# ChameleonMini-RevG.net
KiCad netlist of a schematic drawn in EAGLE
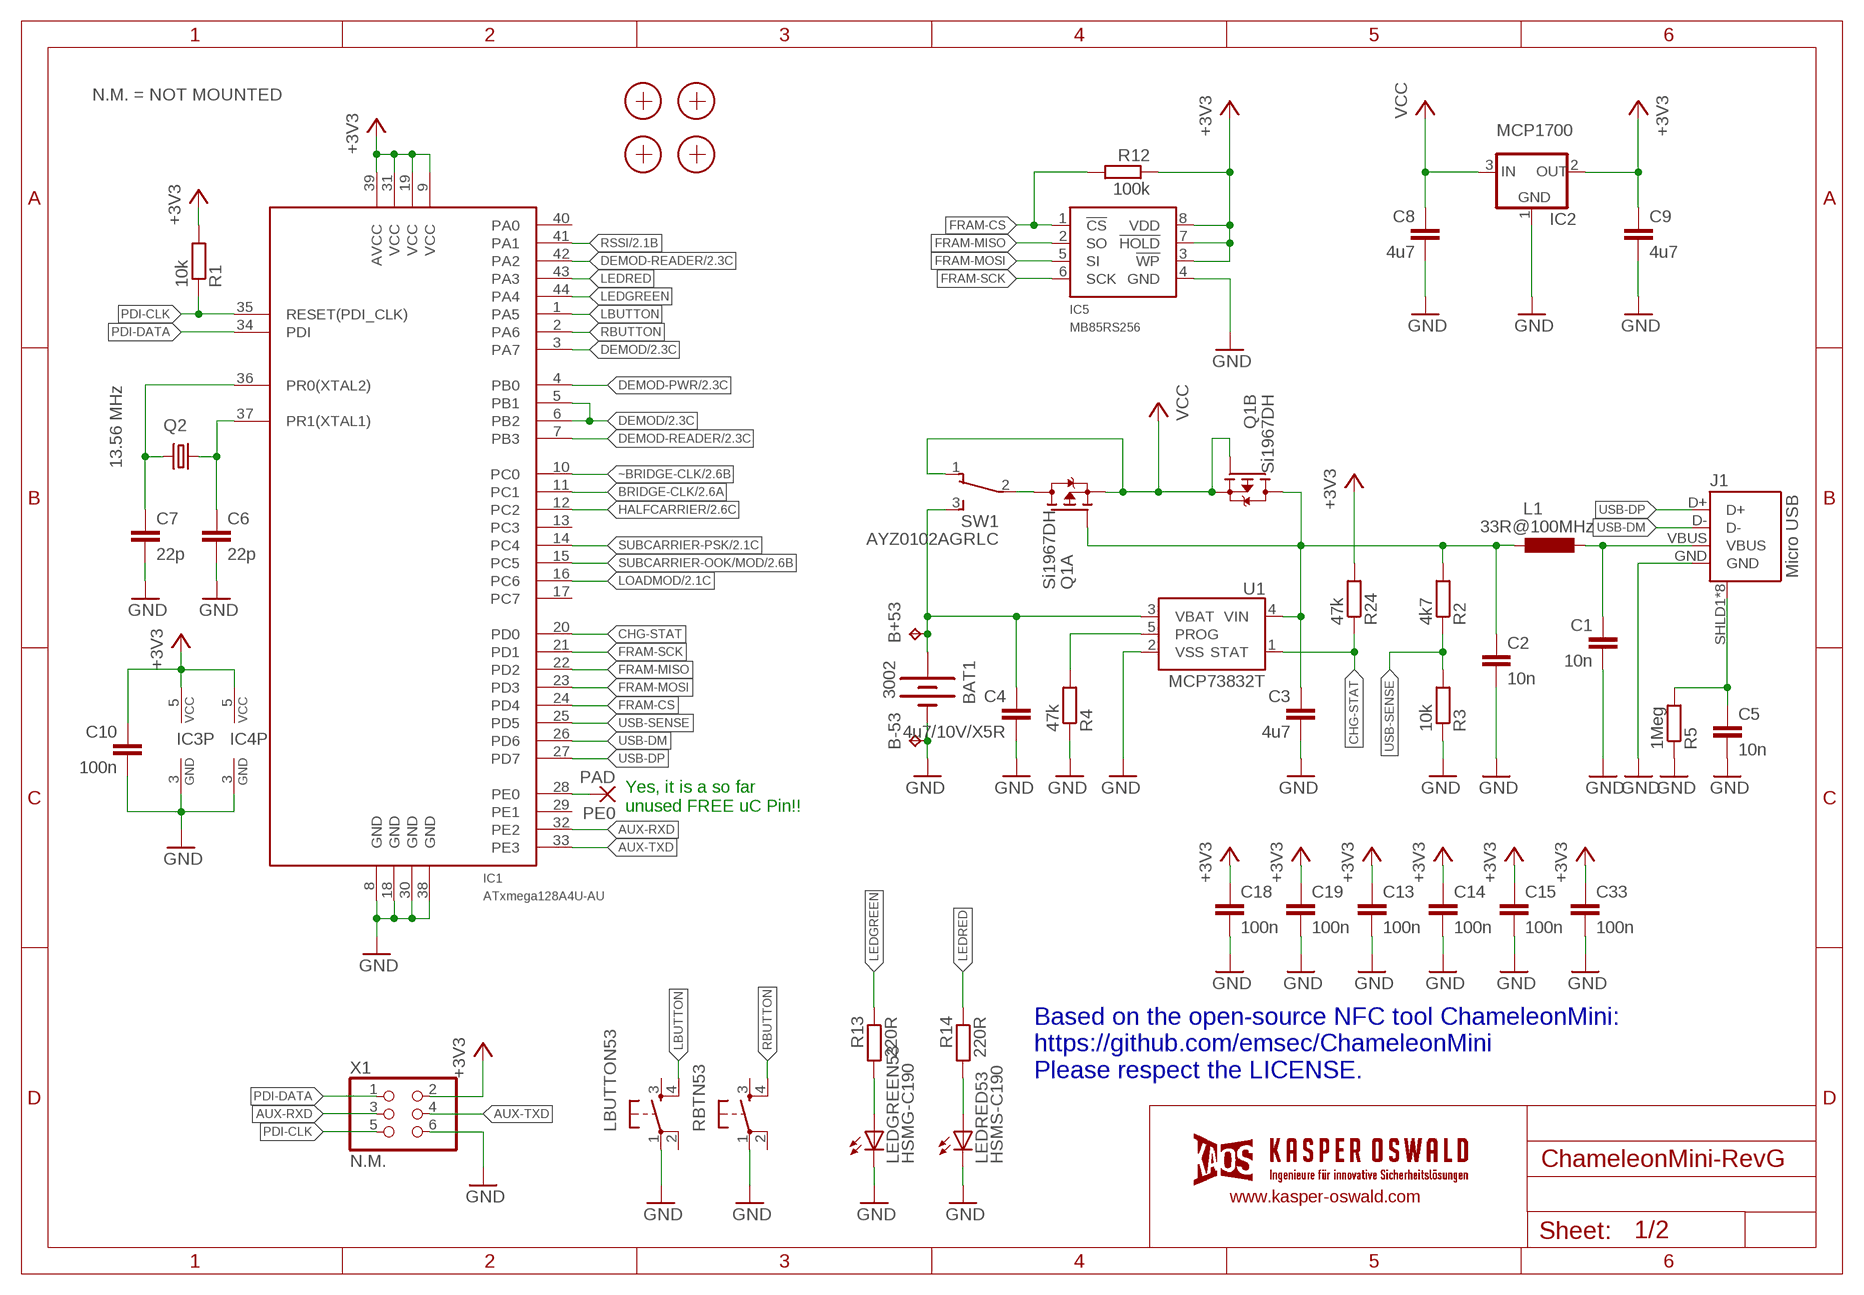
[diagram p0: schematic, sheet 1]
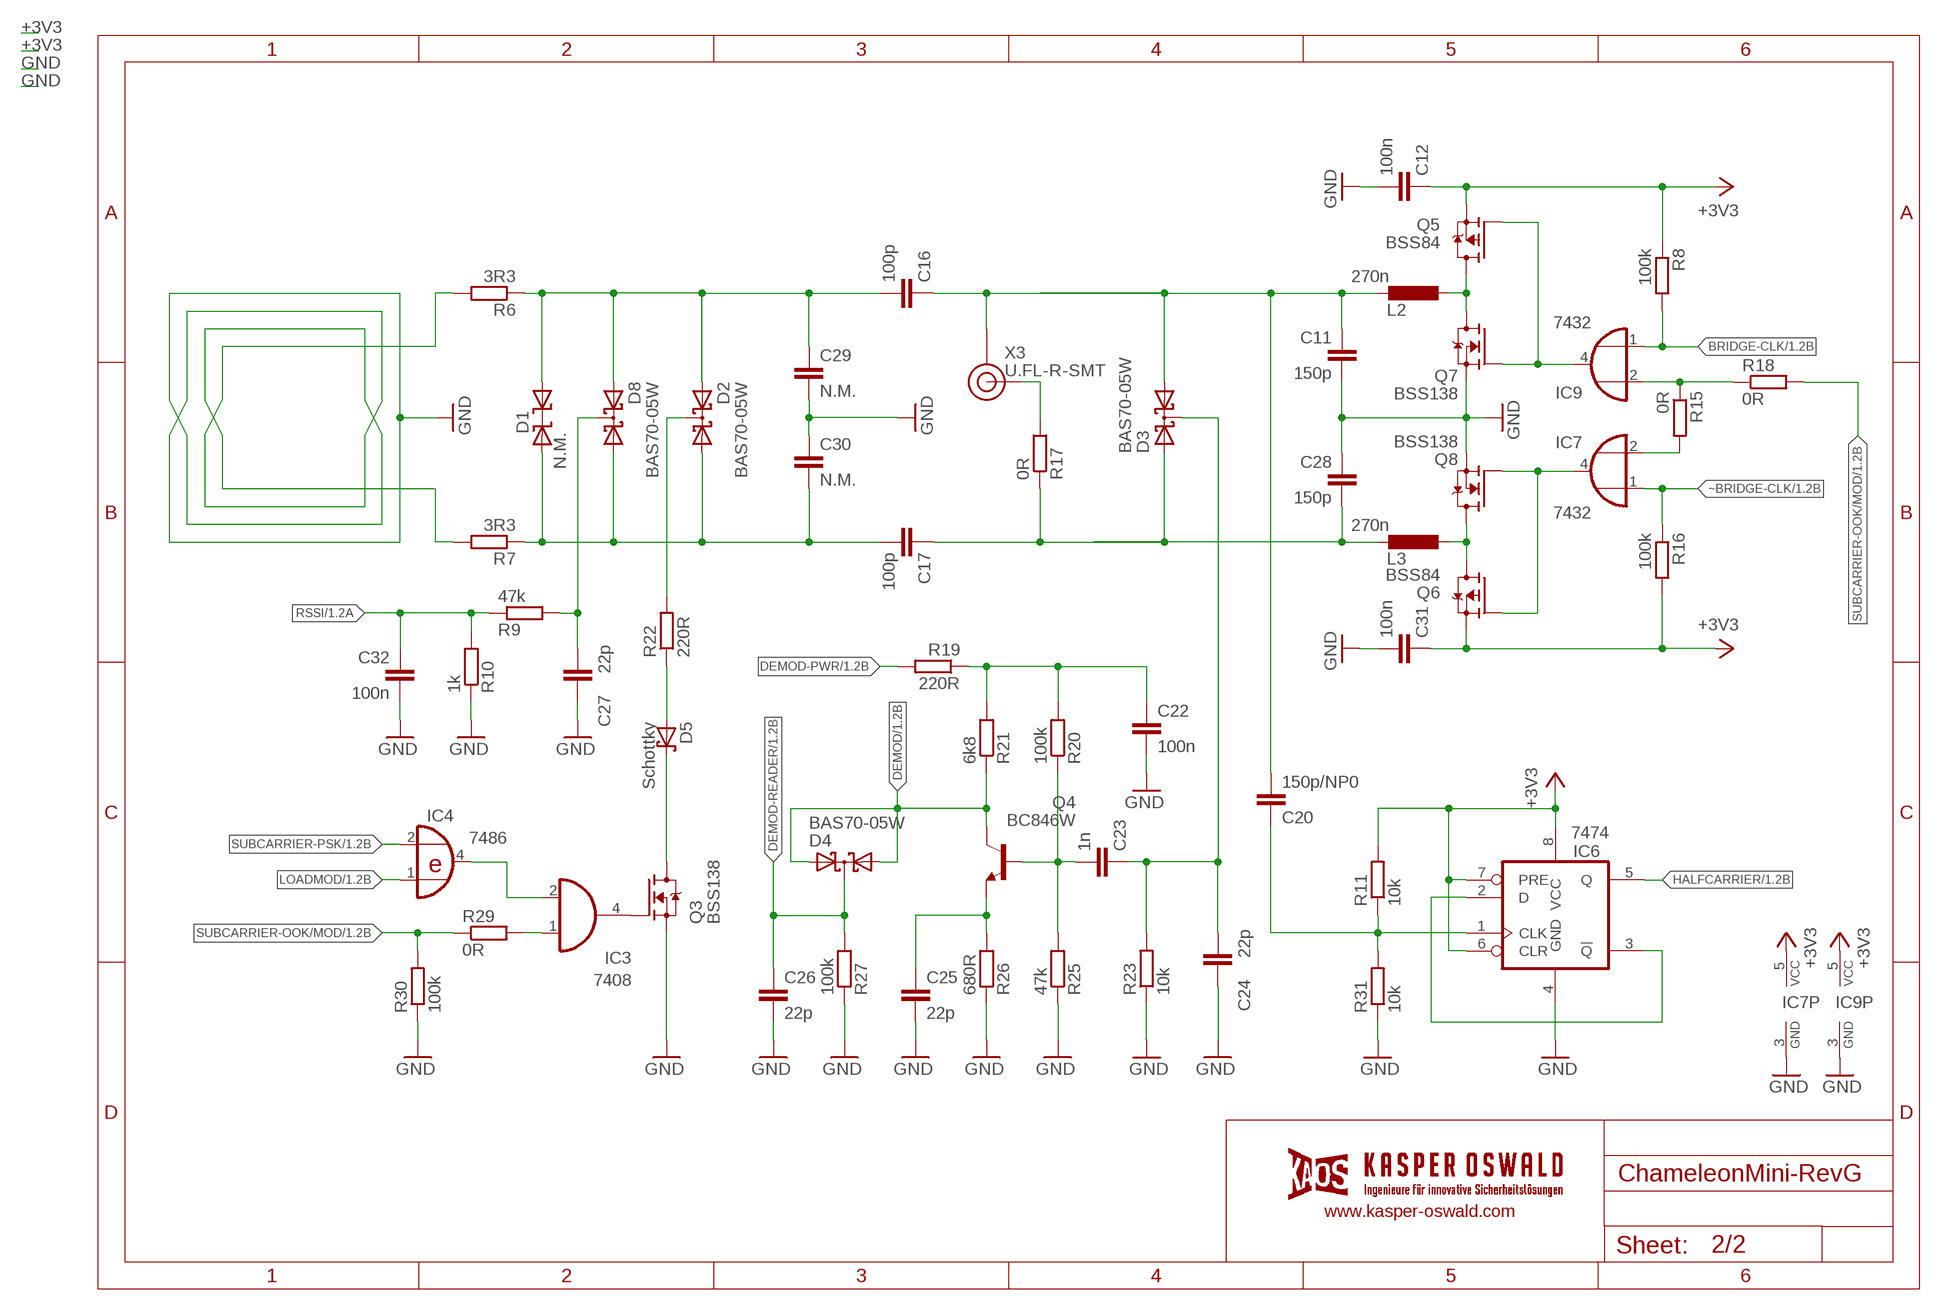
[diagram p1: schematic, sheet 2]

(export (version "E")
  (design (tool "Eeschema 10.0.6"))
  (components
    (comp (ref "C11")
      (value "150p")
      (footprint "eagle-import:C0603K")
      (libsource (lib "eagle-import") (part "C-EUC0603K"))
    )
    (comp (ref "C12")
      (value "100n")
      (footprint "eagle-import:C0603K")
      (libsource (lib "eagle-import") (part "C-EUC0603K"))
    )
    (comp (ref "C16")
      (value "100p")
      (footprint "eagle-import:C0603K")
      (libsource (lib "eagle-import") (part "C-EUC0603K"))
    )
    (comp (ref "C17")
      (value "100p")
      (footprint "eagle-import:C0603K")
      (libsource (lib "eagle-import") (part "C-EUC0603K"))
    )
    (comp (ref "C20")
      (value "150p/NP0")
      (footprint "eagle-import:C0603K")
      (libsource (lib "eagle-import") (part "C-EUC0603K"))
    )
    (comp (ref "C22")
      (value "100n")
      (footprint "eagle-import:C0603K")
      (libsource (lib "eagle-import") (part "C-EUC0603K"))
    )
    (comp (ref "C23")
      (value "1n")
      (footprint "eagle-import:C0603K")
      (libsource (lib "eagle-import") (part "C-EUC0603K"))
    )
    (comp (ref "C24")
      (value "22p")
      (footprint "eagle-import:C0603K")
      (libsource (lib "eagle-import") (part "C-EUC0603K"))
    )
    (comp (ref "C25")
      (value "22p")
      (footprint "eagle-import:C0603K")
      (libsource (lib "eagle-import") (part "C-EUC0603K"))
    )
    (comp (ref "C26")
      (value "22p")
      (footprint "eagle-import:C0603K")
      (libsource (lib "eagle-import") (part "C-EUC0603K"))
    )
    (comp (ref "C27")
      (value "22p")
      (footprint "eagle-import:C0603K")
      (libsource (lib "eagle-import") (part "C-EUC0603K"))
    )
    (comp (ref "C28")
      (value "150p")
      (footprint "eagle-import:C0603K")
      (libsource (lib "eagle-import") (part "C-EUC0603K"))
    )
    (comp (ref "C29")
      (value "N.M.")
      (footprint "eagle-import:C0603K")
      (libsource (lib "eagle-import") (part "C-EUC0603K"))
    )
    (comp (ref "C30")
      (value "N.M.")
      (footprint "eagle-import:C0603K")
      (libsource (lib "eagle-import") (part "C-EUC0603K"))
    )
    (comp (ref "C31")
      (value "100n")
      (footprint "eagle-import:C0603K")
      (libsource (lib "eagle-import") (part "C-EUC0603K"))
    )
    (comp (ref "C32")
      (value "100n")
      (footprint "eagle-import:C0603K")
      (libsource (lib "eagle-import") (part "C-EUC0603K"))
    )
    (comp (ref "D1")
      (value "N.M.")
      (footprint "eagle-import:DO214AC")
      (libsource (lib "eagle-import") (part "SMAJ"))
    )
    (comp (ref "D2")
      (value "BAS70-05W")
      (footprint "eagle-import:SOT323")
      (libsource (lib "eagle-import") (part "BAS70-05W"))
    )
    (comp (ref "D3")
      (value "BAS70-05W")
      (footprint "eagle-import:SOT323")
      (libsource (lib "eagle-import") (part "BAS70-05W"))
    )
    (comp (ref "D4")
      (value "BAS70-05W")
      (footprint "eagle-import:SOT323")
      (libsource (lib "eagle-import") (part "BAS70-05W"))
    )
    (comp (ref "D5")
      (value "Schottky")
      (footprint "eagle-import:SOD323(F)")
      (libsource (lib "eagle-import") (part "1PS76SB70"))
    )
    (comp (ref "D8")
      (value "BAS70-05W")
      (footprint "eagle-import:SOT323")
      (libsource (lib "eagle-import") (part "BAS70-05W"))
    )
    (comp (ref "IC3")
      (value "7408")
      (footprint "eagle-import:SC70-5")
      (libsource (lib "eagle-import") (part "741G08DCKLVC"))
    )
    (comp (ref "IC4")
      (value "7486")
      (footprint "eagle-import:SC70-5")
      (libsource (lib "eagle-import") (part "741G86DCKAHC"))
    )
    (comp (ref "IC6")
      (value "7474")
      (footprint "eagle-import:VSSOP8")
      (libsource (lib "eagle-import") (part "74LVC1G74DC"))
    )
    (comp (ref "IC7")
      (value "7432")
      (footprint "eagle-import:SC70-5")
      (libsource (lib "eagle-import") (part "741G32DCKAHC"))
    )
    (comp (ref "IC9")
      (value "7432")
      (footprint "eagle-import:SC70-5")
      (libsource (lib "eagle-import") (part "741G32DCKAHC"))
    )
    (comp (ref "L2")
      (value "270n")
      (footprint "eagle-import:L2012C")
      (libsource (lib "eagle-import") (part "L-EUL2012C"))
    )
    (comp (ref "L3")
      (value "270n")
      (footprint "eagle-import:L2012C")
      (libsource (lib "eagle-import") (part "L-EUL2012C"))
    )
    (comp (ref "Q3")
      (value "BSS138")
      (footprint "eagle-import:SOT323")
      (libsource (lib "eagle-import") (part "BSS138BKW"))
    )
    (comp (ref "Q4")
      (value "BC846W")
      (footprint "eagle-import:SOT323")
      (libsource (lib "eagle-import") (part "BC84XW"))
    )
    (comp (ref "Q5")
      (value "BSS84")
      (footprint "eagle-import:SOT323")
      (libsource (lib "eagle-import") (part "BSS84AKW"))
    )
    (comp (ref "Q6")
      (value "BSS84")
      (footprint "eagle-import:SOT323")
      (libsource (lib "eagle-import") (part "BSS84AKW"))
    )
    (comp (ref "Q7")
      (value "BSS138")
      (footprint "eagle-import:SOT323")
      (libsource (lib "eagle-import") (part "BSS138BKW"))
    )
    (comp (ref "Q8")
      (value "BSS138")
      (footprint "eagle-import:SOT323")
      (libsource (lib "eagle-import") (part "BSS138BKW"))
    )
    (comp (ref "R6")
      (value "3R3")
      (footprint "eagle-import:R0603")
      (libsource (lib "eagle-import") (part "R-EU_R0603"))
    )
    (comp (ref "R7")
      (value "3R3")
      (footprint "eagle-import:R0603")
      (libsource (lib "eagle-import") (part "R-EU_R0603"))
    )
    (comp (ref "R8")
      (value "100k")
      (footprint "eagle-import:R0603")
      (libsource (lib "eagle-import") (part "R-EU_R0603"))
    )
    (comp (ref "R9")
      (value "47k")
      (footprint "eagle-import:R0603")
      (libsource (lib "eagle-import") (part "R-EU_R0603"))
    )
    (comp (ref "R10")
      (value "1k")
      (footprint "eagle-import:R0603")
      (libsource (lib "eagle-import") (part "R-EU_R0603"))
    )
    (comp (ref "R11")
      (value "10k")
      (footprint "eagle-import:R0603")
      (libsource (lib "eagle-import") (part "R-EU_R0603"))
    )
    (comp (ref "R15")
      (value "0R")
      (footprint "eagle-import:R0603")
      (libsource (lib "eagle-import") (part "R-EU_R0603"))
    )
    (comp (ref "R16")
      (value "100k")
      (footprint "eagle-import:R0603")
      (libsource (lib "eagle-import") (part "R-EU_R0603"))
    )
    (comp (ref "R17")
      (value "0R")
      (footprint "eagle-import:R0603")
      (libsource (lib "eagle-import") (part "R-EU_R0603"))
    )
    (comp (ref "R18")
      (value "0R")
      (footprint "eagle-import:R0603")
      (libsource (lib "eagle-import") (part "R-EU_R0603"))
    )
    (comp (ref "R19")
      (value "220R")
      (footprint "eagle-import:R0603")
      (libsource (lib "eagle-import") (part "R-EU_R0603"))
    )
    (comp (ref "R20")
      (value "100k")
      (footprint "eagle-import:R0603")
      (libsource (lib "eagle-import") (part "R-EU_R0603"))
    )
    (comp (ref "R21")
      (value "6k8")
      (footprint "eagle-import:R0603")
      (libsource (lib "eagle-import") (part "R-EU_R0603"))
    )
    (comp (ref "R22")
      (value "220R")
      (footprint "eagle-import:R0603")
      (libsource (lib "eagle-import") (part "R-EU_R0603"))
    )
    (comp (ref "R23")
      (value "10k")
      (footprint "eagle-import:R0603")
      (libsource (lib "eagle-import") (part "R-EU_R0603"))
    )
    (comp (ref "R25")
      (value "47k")
      (footprint "eagle-import:R0603")
      (libsource (lib "eagle-import") (part "R-EU_R0603"))
    )
    (comp (ref "R26")
      (value "680R")
      (footprint "eagle-import:R0603")
      (libsource (lib "eagle-import") (part "R-EU_R0603"))
    )
    (comp (ref "R27")
      (value "100k")
      (footprint "eagle-import:R0603")
      (libsource (lib "eagle-import") (part "R-EU_R0603"))
    )
    (comp (ref "R29")
      (value "0R")
      (footprint "eagle-import:R0603")
      (libsource (lib "eagle-import") (part "R-EU_R0603"))
    )
    (comp (ref "R30")
      (value "100k")
      (footprint "eagle-import:R0603")
      (libsource (lib "eagle-import") (part "R-EU_R0603"))
    )
    (comp (ref "R31")
      (value "10k")
      (footprint "eagle-import:R0603")
      (libsource (lib "eagle-import") (part "R-EU_R0603"))
    )
    (comp (ref "X3")
      (value "U.FL-R-SMT")
      (footprint "eagle-import:U.FL-R-SMT")
      (libsource (lib "eagle-import") (part "U.FL-R-SMT"))
    )
    (comp (ref "B+53")
      (value "TPTP18SQ")
      (footprint "eagle-import:TP18SQ")
      (libsource (lib "eagle-import") (part "TPTP18SQ"))
    )
    (comp (ref "B-53")
      (value "TPTP18SQ")
      (footprint "eagle-import:TP18SQ")
      (libsource (lib "eagle-import") (part "TPTP18SQ"))
    )
    (comp (ref "BAT1")
      (value "3002")
      (footprint "eagle-import:BATTCON_20MM")
      (libsource (lib "eagle-import") (part "3002"))
    )
    (comp (ref "C1")
      (value "10n")
      (footprint "eagle-import:C1206K")
      (libsource (lib "eagle-import") (part "C-EUC1206K"))
    )
    (comp (ref "C2")
      (value "10n")
      (footprint "eagle-import:C1206K")
      (libsource (lib "eagle-import") (part "C-EUC1206K"))
    )
    (comp (ref "C3")
      (value "4u7")
      (footprint "eagle-import:C0603K")
      (libsource (lib "eagle-import") (part "C-EUC0603K"))
    )
    (comp (ref "C4")
      (value "4u7/10V/X5R")
      (footprint "eagle-import:C0603K")
      (libsource (lib "eagle-import") (part "C-EUC0603K"))
    )
    (comp (ref "C5")
      (value "10n")
      (footprint "eagle-import:C0603K")
      (libsource (lib "eagle-import") (part "C-EUC0603K"))
    )
    (comp (ref "C6")
      (value "22p")
      (footprint "eagle-import:C0603K")
      (libsource (lib "eagle-import") (part "C-EUC0603K"))
    )
    (comp (ref "C7")
      (value "22p")
      (footprint "eagle-import:C0603K")
      (libsource (lib "eagle-import") (part "C-EUC0603K"))
    )
    (comp (ref "C8")
      (value "4u7")
      (footprint "eagle-import:C0603K")
      (libsource (lib "eagle-import") (part "C-EUC0603K"))
    )
    (comp (ref "C9")
      (value "4u7")
      (footprint "eagle-import:C0603K")
      (libsource (lib "eagle-import") (part "C-EUC0603K"))
    )
    (comp (ref "C10")
      (value "100n")
      (footprint "eagle-import:C0603K")
      (libsource (lib "eagle-import") (part "C-EUC0603K"))
    )
    (comp (ref "C13")
      (value "100n")
      (footprint "eagle-import:C0603K")
      (libsource (lib "eagle-import") (part "C-EUC0603K"))
    )
    (comp (ref "C14")
      (value "100n")
      (footprint "eagle-import:C0603K")
      (libsource (lib "eagle-import") (part "C-EUC0603K"))
    )
    (comp (ref "C15")
      (value "100n")
      (footprint "eagle-import:C0603K")
      (libsource (lib "eagle-import") (part "C-EUC0603K"))
    )
    (comp (ref "C18")
      (value "100n")
      (footprint "eagle-import:C0603K")
      (libsource (lib "eagle-import") (part "C-EUC0603K"))
    )
    (comp (ref "C19")
      (value "100n")
      (footprint "eagle-import:C0603K")
      (libsource (lib "eagle-import") (part "C-EUC0603K"))
    )
    (comp (ref "C33")
      (value "100n")
      (footprint "eagle-import:C0603K")
      (libsource (lib "eagle-import") (part "C-EUC0603K"))
    )
    (comp (ref "IC1")
      (value "ATxmega128A4U-AU")
      (footprint "eagle-import:TQFP44")
      (libsource (lib "eagle-import") (part "ATXMEGA_A4-A"))
    )
    (comp (ref "IC2")
      (value "MCP1700")
      (footprint "eagle-import:SOT23")
      (libsource (lib "eagle-import") (part "MCP1702"))
    )
    (comp (ref "IC5")
      (value "MB85RS256")
      (footprint "eagle-import:SO-08")
      (libsource (lib "eagle-import") (part "MB85RS"))
    )
    (comp (ref "J1")
      (value "Micro USB")
      (footprint "eagle-import:USB-MICROB-10118194")
      (libsource (lib "eagle-import") (part "USB-MICROB-2"))
    )
    (comp (ref "L1")
      (value "33R@100MHz")
      (footprint "eagle-import:L2012C")
      (libsource (lib "eagle-import") (part "L-EUL2012C"))
    )
    (comp (ref "LBUTTON53")
      (value "SWITCH_SPST_4_PINSQUARE")
      (footprint "eagle-import:TACTILE-SWITCH-SMD")
      (libsource (lib "eagle-import") (part "SWITCH_SPST_4_PINSQUARE"))
    )
    (comp (ref "LEDGREEN53")
      (value "HSMG-C190")
      (footprint "eagle-import:CHIPLED-0603")
      (libsource (lib "eagle-import") (part "LED-0603"))
    )
    (comp (ref "LEDRED53")
      (value "HSMS-C190")
      (footprint "eagle-import:CHIPLED-0603")
      (libsource (lib "eagle-import") (part "LED-0603"))
    )
    (comp (ref "PE0")
      (value "PAD")
      (footprint "eagle-import:SMD1,27-2,54")
      (libsource (lib "eagle-import") (part "WIREPADSMD1,27-254"))
    )
    (comp (ref "Q1")
      (value "Si1967DH")
      (footprint "eagle-import:SOT363")
      (libsource (lib "eagle-import") (part "BSS84AKS"))
    )
    (comp (ref "Q2")
      (value "13.56 MHz")
      (footprint "eagle-import:5MMX3.2MM")
      (libsource (lib "eagle-import") (part "TXC7B"))
    )
    (comp (ref "R1")
      (value "10k")
      (footprint "eagle-import:R0603")
      (libsource (lib "eagle-import") (part "R-EU_R0603"))
    )
    (comp (ref "R2")
      (value "4k7")
      (footprint "eagle-import:R0603")
      (libsource (lib "eagle-import") (part "R-EU_R0603"))
    )
    (comp (ref "R3")
      (value "10k")
      (footprint "eagle-import:R0603")
      (libsource (lib "eagle-import") (part "R-EU_R0603"))
    )
    (comp (ref "R4")
      (value "47k")
      (footprint "eagle-import:R0603")
      (libsource (lib "eagle-import") (part "R-EU_R0603"))
    )
    (comp (ref "R5")
      (value "1Meg")
      (footprint "eagle-import:R0603")
      (libsource (lib "eagle-import") (part "R-EU_R0603"))
    )
    (comp (ref "R12")
      (value "100k")
      (footprint "eagle-import:R0603")
      (libsource (lib "eagle-import") (part "R-EU_R0603"))
    )
    (comp (ref "R13")
      (value "220R")
      (footprint "eagle-import:R0603")
      (libsource (lib "eagle-import") (part "R-EU_R0603"))
    )
    (comp (ref "R14")
      (value "220R")
      (footprint "eagle-import:R0603")
      (libsource (lib "eagle-import") (part "R-EU_R0603"))
    )
    (comp (ref "R24")
      (value "47k")
      (footprint "eagle-import:R0603")
      (libsource (lib "eagle-import") (part "R-EU_R0603"))
    )
    (comp (ref "RBTN53")
      (value "SWITCH_SPST_4_PINSQUARE")
      (footprint "eagle-import:TACTILE-SWITCH-SMD")
      (libsource (lib "eagle-import") (part "SWITCH_SPST_4_PINSQUARE"))
    )
    (comp (ref "SW1")
      (value "AYZ0102AGRLC")
      (footprint "eagle-import:AYZ0102AGRLC")
      (libsource (lib "eagle-import") (part "AYZ0102AGRLC"))
    )
    (comp (ref "U1")
      (value "MCP73832T")
      (footprint "eagle-import:SOT23-5")
      (libsource (lib "eagle-import") (part "MCP73831"))
    )
    (comp (ref "X1")
      (value "N.M.")
      (footprint "eagle-import:PINHD-2X3-2.54-EDGE")
      (libsource (lib "eagle-import") (part "PINHD-2X3-2.54-EDGE"))
    )
    (comp (ref "X2")
      (value "PASSER-07")
      (footprint "eagle-import:PASSER_07MM")
      (libsource (lib "eagle-import") (part "PASSER-07"))
    )
    (comp (ref "X4")
      (value "PASSER-07")
      (footprint "eagle-import:PASSER_07MM")
      (libsource (lib "eagle-import") (part "PASSER-07"))
    )
    (comp (ref "X5")
      (value "PASSER-07")
      (footprint "eagle-import:PASSER_07MM")
      (libsource (lib "eagle-import") (part "PASSER-07"))
    )
    (comp (ref "X6")
      (value "PASSER-07")
      (footprint "eagle-import:PASSER_07MM")
      (libsource (lib "eagle-import") (part "PASSER-07"))
    )
  )
  (nets
    (net (code "1") (name "+3V3") (class "Default")
      (node (ref "C10") (pin "1") (pinfunction "1_1") (pintype "passive"))
      (node (ref "C12") (pin "1") (pinfunction "1_1") (pintype "passive"))
      (node (ref "C13") (pin "1") (pinfunction "1_1") (pintype "passive"))
      (node (ref "C14") (pin "1") (pinfunction "1_1") (pintype "passive"))
      (node (ref "C15") (pin "1") (pinfunction "1_1") (pintype "passive"))
      (node (ref "C18") (pin "1") (pinfunction "1_1") (pintype "passive"))
      (node (ref "C19") (pin "1") (pinfunction "1_1") (pintype "passive"))
      (node (ref "C31") (pin "1") (pinfunction "1_1") (pintype "passive"))
      (node (ref "C33") (pin "1") (pinfunction "1_1") (pintype "passive"))
      (node (ref "C9") (pin "1") (pinfunction "1_1") (pintype "passive"))
      (node (ref "IC1") (pin "19") (pinfunction "VCC_19") (pintype "bidirectional"))
      (node (ref "IC1") (pin "31") (pinfunction "VCC_31") (pintype "bidirectional"))
      (node (ref "IC1") (pin "39") (pinfunction "AVCC_39") (pintype "bidirectional"))
      (node (ref "IC1") (pin "9") (pinfunction "VCC_9") (pintype "bidirectional"))
      (node (ref "IC2") (pin "2") (pinfunction "OUT_2") (pintype "passive"))
      (node (ref "IC3") (pin "5") (pinfunction "VCC_5") (pintype "power_in"))
      (node (ref "IC4") (pin "5") (pinfunction "VCC_5") (pintype "power_in"))
      (node (ref "IC5") (pin "3") (pinfunction "~{WP}_3") (pintype "bidirectional"))
      (node (ref "IC5") (pin "7") (pinfunction "~{HOLD}_7") (pintype "bidirectional"))
      (node (ref "IC5") (pin "8") (pinfunction "VDD_8") (pintype "bidirectional"))
      (node (ref "IC6") (pin "6") (pinfunction "CLR_6") (pintype "input"))
      (node (ref "IC6") (pin "7") (pinfunction "PRE_7") (pintype "input"))
      (node (ref "IC6") (pin "8") (pinfunction "VCC_8") (pintype "bidirectional"))
      (node (ref "IC7") (pin "5") (pinfunction "VCC_5") (pintype "power_in"))
      (node (ref "IC9") (pin "5") (pinfunction "VCC_5") (pintype "power_in"))
      (node (ref "Q5") (pin "2") (pinfunction "S_2") (pintype "passive"))
      (node (ref "Q6") (pin "2") (pinfunction "S_2") (pintype "passive"))
      (node (ref "R1") (pin "2") (pinfunction "2_2") (pintype "passive"))
      (node (ref "R11") (pin "2") (pinfunction "2_2") (pintype "passive"))
      (node (ref "R12") (pin "1") (pinfunction "1_1") (pintype "passive"))
      (node (ref "R16") (pin "2") (pinfunction "2_2") (pintype "passive"))
      (node (ref "R24") (pin "2") (pinfunction "2_2") (pintype "passive"))
      (node (ref "R8") (pin "1") (pinfunction "1_1") (pintype "passive"))
      (node (ref "X1") (pin "2") (pinfunction "2_2") (pintype "passive"))
    )
    (net (code "2") (name "AUX-RXD") (class "Default")
      (node (ref "IC1") (pin "32") (pinfunction "PE2_32") (pintype "bidirectional"))
      (node (ref "X1") (pin "3") (pinfunction "3_3") (pintype "passive"))
    )
    (net (code "3") (name "AUX-TXD") (class "Default")
      (node (ref "IC1") (pin "33") (pinfunction "PE3_33") (pintype "bidirectional"))
      (node (ref "X1") (pin "4") (pinfunction "4_4") (pintype "passive"))
    )
    (net (code "4") (name "BRIDGE-CLK") (class "Default")
      (node (ref "IC1") (pin "11") (pinfunction "PC1_11") (pintype "bidirectional"))
      (node (ref "IC9") (pin "1") (pinfunction "I0_1") (pintype "input"))
      (node (ref "R8") (pin "2") (pinfunction "2_2") (pintype "passive"))
    )
    (net (code "5") (name "CHG-STAT") (class "Default")
      (node (ref "IC1") (pin "20") (pinfunction "PD0_20") (pintype "bidirectional"))
      (node (ref "R24") (pin "1") (pinfunction "1_1") (pintype "passive"))
      (node (ref "U1") (pin "1") (pinfunction "STAT_1") (pintype "output"))
    )
    (net (code "6") (name "DEMOD") (class "Default")
      (node (ref "D4") (pin "1") (pinfunction "A1_1") (pintype "passive"))
      (node (ref "D4") (pin "2") (pinfunction "A2_2") (pintype "passive"))
      (node (ref "IC1") (pin "3") (pinfunction "PA7_3") (pintype "bidirectional"))
      (node (ref "IC1") (pin "5") (pinfunction "PB1_5") (pintype "bidirectional"))
      (node (ref "IC1") (pin "6") (pinfunction "PB2_6") (pintype "bidirectional"))
      (node (ref "Q4") (pin "3") (pinfunction "C_3") (pintype "passive"))
      (node (ref "R21") (pin "1") (pinfunction "1_1") (pintype "passive"))
    )
    (net (code "7") (name "DEMOD-PWR") (class "Default")
      (node (ref "IC1") (pin "4") (pinfunction "PB0_4") (pintype "bidirectional"))
      (node (ref "R19") (pin "2") (pinfunction "2_2") (pintype "passive"))
    )
    (net (code "8") (name "DEMOD-READER") (class "Default")
      (node (ref "C26") (pin "1") (pinfunction "1_1") (pintype "passive"))
      (node (ref "D4") (pin "3") (pinfunction "K_3") (pintype "passive"))
      (node (ref "IC1") (pin "42") (pinfunction "PA2_42") (pintype "bidirectional"))
      (node (ref "IC1") (pin "7") (pinfunction "PB3_7") (pintype "bidirectional"))
      (node (ref "R27") (pin "2") (pinfunction "2_2") (pintype "passive"))
    )
    (net (code "9") (name "FRAM-CS") (class "Default")
      (node (ref "IC1") (pin "24") (pinfunction "PD4_24") (pintype "bidirectional"))
      (node (ref "IC5") (pin "1") (pinfunction "~{CS}_1") (pintype "bidirectional"))
      (node (ref "R12") (pin "2") (pinfunction "2_2") (pintype "passive"))
    )
    (net (code "10") (name "FRAM-MISO") (class "Default")
      (node (ref "IC1") (pin "22") (pinfunction "PD2_22") (pintype "bidirectional"))
      (node (ref "IC5") (pin "2") (pinfunction "SO_2") (pintype "bidirectional"))
    )
    (net (code "11") (name "FRAM-MOSI") (class "Default")
      (node (ref "IC1") (pin "23") (pinfunction "PD3_23") (pintype "bidirectional"))
      (node (ref "IC5") (pin "5") (pinfunction "SI_5") (pintype "bidirectional"))
    )
    (net (code "12") (name "FRAM-SCK") (class "Default")
      (node (ref "IC1") (pin "21") (pinfunction "PD1_21") (pintype "bidirectional"))
      (node (ref "IC5") (pin "6") (pinfunction "SCK_6") (pintype "bidirectional"))
    )
    (net (code "13") (name "GND") (class "Default")
      (node (ref "B-53") (pin "TP") (pinfunction "TP_TP") (pintype "input"))
      (node (ref "BAT1") (pin "-") (pinfunction "-_-") (pintype "power_in"))
      (node (ref "C1") (pin "2") (pinfunction "2_2") (pintype "passive"))
      (node (ref "C10") (pin "2") (pinfunction "2_2") (pintype "passive"))
      (node (ref "C11") (pin "2") (pinfunction "2_2") (pintype "passive"))
      (node (ref "C12") (pin "2") (pinfunction "2_2") (pintype "passive"))
      (node (ref "C13") (pin "2") (pinfunction "2_2") (pintype "passive"))
      (node (ref "C14") (pin "2") (pinfunction "2_2") (pintype "passive"))
      (node (ref "C15") (pin "2") (pinfunction "2_2") (pintype "passive"))
      (node (ref "C18") (pin "2") (pinfunction "2_2") (pintype "passive"))
      (node (ref "C19") (pin "2") (pinfunction "2_2") (pintype "passive"))
      (node (ref "C2") (pin "2") (pinfunction "2_2") (pintype "passive"))
      (node (ref "C22") (pin "2") (pinfunction "2_2") (pintype "passive"))
      (node (ref "C24") (pin "2") (pinfunction "2_2") (pintype "passive"))
      (node (ref "C25") (pin "2") (pinfunction "2_2") (pintype "passive"))
      (node (ref "C26") (pin "2") (pinfunction "2_2") (pintype "passive"))
      (node (ref "C27") (pin "2") (pinfunction "2_2") (pintype "passive"))
      (node (ref "C28") (pin "1") (pinfunction "1_1") (pintype "passive"))
      (node (ref "C29") (pin "2") (pinfunction "2_2") (pintype "passive"))
      (node (ref "C3") (pin "2") (pinfunction "2_2") (pintype "passive"))
      (node (ref "C30") (pin "1") (pinfunction "1_1") (pintype "passive"))
      (node (ref "C31") (pin "2") (pinfunction "2_2") (pintype "passive"))
      (node (ref "C32") (pin "2") (pinfunction "2_2") (pintype "passive"))
      (node (ref "C33") (pin "2") (pinfunction "2_2") (pintype "passive"))
      (node (ref "C4") (pin "2") (pinfunction "2_2") (pintype "passive"))
      (node (ref "C5") (pin "2") (pinfunction "2_2") (pintype "passive"))
      (node (ref "C6") (pin "2") (pinfunction "2_2") (pintype "passive"))
      (node (ref "C7") (pin "2") (pinfunction "2_2") (pintype "passive"))
      (node (ref "C8") (pin "2") (pinfunction "2_2") (pintype "passive"))
      (node (ref "C9") (pin "2") (pinfunction "2_2") (pintype "passive"))
      (node (ref "IC1") (pin "18") (pinfunction "GND_18") (pintype "bidirectional"))
      (node (ref "IC1") (pin "30") (pinfunction "GND_30") (pintype "bidirectional"))
      (node (ref "IC1") (pin "38") (pinfunction "GND_38") (pintype "bidirectional"))
      (node (ref "IC1") (pin "8") (pinfunction "GND_8") (pintype "bidirectional"))
      (node (ref "IC2") (pin "1") (pinfunction "GND_1") (pintype "input"))
      (node (ref "IC3") (pin "3") (pinfunction "GND_3") (pintype "power_in"))
      (node (ref "IC4") (pin "3") (pinfunction "GND_3") (pintype "power_in"))
      (node (ref "IC5") (pin "4") (pinfunction "GND_4") (pintype "bidirectional"))
      (node (ref "IC6") (pin "4") (pinfunction "GND_4") (pintype "bidirectional"))
      (node (ref "IC7") (pin "3") (pinfunction "GND_3") (pintype "power_in"))
      (node (ref "IC9") (pin "3") (pinfunction "GND_3") (pintype "power_in"))
      (node (ref "J1") (pin "GND") (pinfunction "GND_GND") (pintype "power_in"))
      (node (ref "LBUTTON53") (pin "1") (pinfunction "1_1") (pintype "passive"))
      (node (ref "LEDGREEN53") (pin "C") (pinfunction "C_C") (pintype "passive"))
      (node (ref "LEDRED53") (pin "C") (pinfunction "C_C") (pintype "passive"))
      (node (ref "Q3") (pin "2") (pinfunction "S_2") (pintype "passive"))
      (node (ref "Q7") (pin "2") (pinfunction "S_2") (pintype "passive"))
      (node (ref "Q8") (pin "2") (pinfunction "S_2") (pintype "passive"))
      (node (ref "R10") (pin "1") (pinfunction "1_1") (pintype "passive"))
      (node (ref "R23") (pin "1") (pinfunction "1_1") (pintype "passive"))
      (node (ref "R25") (pin "1") (pinfunction "1_1") (pintype "passive"))
      (node (ref "R26") (pin "1") (pinfunction "1_1") (pintype "passive"))
      (node (ref "R27") (pin "1") (pinfunction "1_1") (pintype "passive"))
      (node (ref "R3") (pin "1") (pinfunction "1_1") (pintype "passive"))
      (node (ref "R30") (pin "1") (pinfunction "1_1") (pintype "passive"))
      (node (ref "R31") (pin "1") (pinfunction "1_1") (pintype "passive"))
      (node (ref "R4") (pin "1") (pinfunction "1_1") (pintype "passive"))
      (node (ref "R5") (pin "1") (pinfunction "1_1") (pintype "passive"))
      (node (ref "R6") (pin "2") (pinfunction "2_2") (pintype "passive"))
      (node (ref "R7") (pin "2") (pinfunction "2_2") (pintype "passive"))
      (node (ref "RBTN53") (pin "1") (pinfunction "1_1") (pintype "passive"))
      (node (ref "U1") (pin "2") (pinfunction "VSS_2") (pintype "power_in"))
      (node (ref "X1") (pin "6") (pinfunction "6_6") (pintype "passive"))
    )
    (net (code "14") (name "HALFCARRIER") (class "Default")
      (node (ref "IC1") (pin "12") (pinfunction "PC2_12") (pintype "bidirectional"))
      (node (ref "IC6") (pin "5") (pinfunction "Q_5") (pintype "output"))
    )
    (net (code "15") (name "LBUTTON") (class "Default")
      (node (ref "IC1") (pin "1") (pinfunction "PA5_1") (pintype "bidirectional"))
      (node (ref "LBUTTON53") (pin "4") (pinfunction "4_4") (pintype "passive"))
    )
    (net (code "16") (name "LEDGREEN") (class "Default")
      (node (ref "IC1") (pin "44") (pinfunction "PA4_44") (pintype "bidirectional"))
      (node (ref "R13") (pin "1") (pinfunction "1_1") (pintype "passive"))
    )
    (net (code "17") (name "LEDRED") (class "Default")
      (node (ref "IC1") (pin "43") (pinfunction "PA3_43") (pintype "bidirectional"))
      (node (ref "R14") (pin "1") (pinfunction "1_1") (pintype "passive"))
    )
    (net (code "18") (name "LOADMOD") (class "Default")
      (node (ref "IC1") (pin "16") (pinfunction "PC6_16") (pintype "bidirectional"))
      (node (ref "IC4") (pin "1") (pinfunction "I0_1") (pintype "input"))
    )
    (net (code "19") (name "Net-(BAT1-+)") (class "Default")
      (node (ref "B+53") (pin "TP") (pinfunction "TP_TP") (pintype "input"))
      (node (ref "BAT1") (pin "+2") (pinfunction "+_+2") (pintype "power_in"))
      (node (ref "C4") (pin "1") (pinfunction "1_1") (pintype "passive"))
      (node (ref "SW1") (pin "3") (pinfunction "S_3") (pintype "passive"))
      (node (ref "U1") (pin "3") (pinfunction "VBAT_3") (pintype "power_in"))
    )
    (net (code "20") (name "Net-(C1-Pad1)") (class "Default")
      (node (ref "C1") (pin "1") (pinfunction "1_1") (pintype "passive"))
      (node (ref "J1") (pin "VBUS") (pinfunction "VBUS_VBUS") (pintype "power_in"))
      (node (ref "L1") (pin "1") (pinfunction "1_1") (pintype "passive"))
    )
    (net (code "21") (name "Net-(C5-Pad1)") (class "Default")
      (node (ref "C5") (pin "1") (pinfunction "1_1") (pintype "passive"))
      (node (ref "J1") (pin "SHLD1") (pinfunction "SHIELD_SHLD1") (pintype "passive"))
      (node (ref "J1") (pin "SHLD2") (pinfunction "SHIELD_SHLD2") (pintype "passive"))
      (node (ref "J1") (pin "SHLD3") (pinfunction "SHIELD_SHLD3") (pintype "passive"))
      (node (ref "J1") (pin "SHLD4") (pinfunction "SHIELD_SHLD4") (pintype "passive"))
      (node (ref "J1") (pin "SHLD5") (pinfunction "SHIELD_SHLD5") (pintype "passive"))
      (node (ref "J1") (pin "SHLD6") (pinfunction "SHIELD_SHLD6") (pintype "passive"))
      (node (ref "J1") (pin "SHLD7") (pinfunction "SHIELD_SHLD7") (pintype "passive"))
      (node (ref "J1") (pin "SHLD8") (pinfunction "SHIELD_SHLD8") (pintype "passive"))
      (node (ref "R5") (pin "2") (pinfunction "2_2") (pintype "passive"))
    )
    (net (code "22") (name "Net-(C22-Pad1)") (class "Default")
      (node (ref "C22") (pin "1") (pinfunction "1_1") (pintype "passive"))
      (node (ref "R19") (pin "1") (pinfunction "1_1") (pintype "passive"))
      (node (ref "R20") (pin "2") (pinfunction "2_2") (pintype "passive"))
      (node (ref "R21") (pin "2") (pinfunction "2_2") (pintype "passive"))
    )
    (net (code "23") (name "Net-(D2-A1)") (class "Default")
      (node (ref "C16") (pin "2") (pinfunction "2_2") (pintype "passive"))
      (node (ref "C29") (pin "1") (pinfunction "1_1") (pintype "passive"))
      (node (ref "D1") (pin "2") (pinfunction "2_2") (pintype "passive"))
      (node (ref "D2") (pin "1") (pinfunction "A1_1") (pintype "passive"))
      (node (ref "D8") (pin "1") (pinfunction "A1_1") (pintype "passive"))
      (node (ref "R6") (pin "1") (pinfunction "1_1") (pintype "passive"))
    )
    (net (code "24") (name "Net-(D2-A2)") (class "Default")
      (node (ref "C17") (pin "2") (pinfunction "2_2") (pintype "passive"))
      (node (ref "C30") (pin "2") (pinfunction "2_2") (pintype "passive"))
      (node (ref "D1") (pin "1") (pinfunction "1_1") (pintype "passive"))
      (node (ref "D2") (pin "2") (pinfunction "A2_2") (pintype "passive"))
      (node (ref "D8") (pin "2") (pinfunction "A2_2") (pintype "passive"))
      (node (ref "R7") (pin "1") (pinfunction "1_1") (pintype "passive"))
    )
    (net (code "25") (name "Net-(D2-K)") (class "Default")
      (node (ref "D2") (pin "3") (pinfunction "K_3") (pintype "passive"))
      (node (ref "R22") (pin "2") (pinfunction "2_2") (pintype "passive"))
    )
    (net (code "26") (name "Net-(D3-A1)") (class "Default")
      (node (ref "C17") (pin "1") (pinfunction "1_1") (pintype "passive"))
      (node (ref "C28") (pin "2") (pinfunction "2_2") (pintype "passive"))
      (node (ref "D3") (pin "1") (pinfunction "A1_1") (pintype "passive"))
      (node (ref "L3") (pin "2") (pinfunction "2_2") (pintype "passive"))
      (node (ref "R17") (pin "1") (pinfunction "1_1") (pintype "passive"))
    )
    (net (code "27") (name "Net-(D3-A2)") (class "Default")
      (node (ref "C11") (pin "1") (pinfunction "1_1") (pintype "passive"))
      (node (ref "C16") (pin "1") (pinfunction "1_1") (pintype "passive"))
      (node (ref "C20") (pin "2") (pinfunction "2_2") (pintype "passive"))
      (node (ref "D3") (pin "2") (pinfunction "A2_2") (pintype "passive"))
      (node (ref "L2") (pin "2") (pinfunction "2_2") (pintype "passive"))
      (node (ref "X3") (pin "GND1") (pinfunction "GND_GND1") (pintype "bidirectional"))
    )
    (net (code "28") (name "Net-(D3-K)") (class "Default")
      (node (ref "C23") (pin "1") (pinfunction "1_1") (pintype "passive"))
      (node (ref "C24") (pin "1") (pinfunction "1_1") (pintype "passive"))
      (node (ref "D3") (pin "3") (pinfunction "K_3") (pintype "passive"))
      (node (ref "R23") (pin "2") (pinfunction "2_2") (pintype "passive"))
    )
    (net (code "29") (name "Net-(D5-A)") (class "Default")
      (node (ref "D5") (pin "2") (pinfunction "A_2") (pintype "passive"))
      (node (ref "R22") (pin "1") (pinfunction "1_1") (pintype "passive"))
    )
    (net (code "30") (name "Net-(D5-K)") (class "Default")
      (node (ref "D5") (pin "1") (pinfunction "K_1") (pintype "passive"))
      (node (ref "Q3") (pin "3") (pinfunction "D_3") (pintype "passive"))
    )
    (net (code "31") (name "Net-(D8-K)") (class "Default")
      (node (ref "C27") (pin "1") (pinfunction "1_1") (pintype "passive"))
      (node (ref "D8") (pin "3") (pinfunction "K_3") (pintype "passive"))
      (node (ref "R9") (pin "2") (pinfunction "2_2") (pintype "passive"))
    )
    (net (code "32") (name "Net-(IC1-PE0)") (class "Default")
      (node (ref "IC1") (pin "28") (pinfunction "PE0_28") (pintype "bidirectional"))
      (node (ref "PE0") (pin "1") (pinfunction "P_1") (pintype "passive"))
    )
    (net (code "33") (name "Net-(IC1-PR0(XTAL2))") (class "Default")
      (node (ref "C7") (pin "1") (pinfunction "1_1") (pintype "passive"))
      (node (ref "IC1") (pin "36") (pinfunction "PR0(XTAL2)_36") (pintype "bidirectional"))
      (node (ref "Q2") (pin "3") (pinfunction "2_3") (pintype "passive"))
    )
    (net (code "34") (name "Net-(IC1-PR1(XTAL1))") (class "Default")
      (node (ref "C6") (pin "1") (pinfunction "1_1") (pintype "passive"))
      (node (ref "IC1") (pin "37") (pinfunction "PR1(XTAL1)_37") (pintype "bidirectional"))
      (node (ref "Q2") (pin "1") (pinfunction "1_1") (pintype "passive"))
    )
    (net (code "35") (name "Net-(IC3A-I0)") (class "Default")
      (node (ref "IC3") (pin "1") (pinfunction "I0_1") (pintype "input"))
      (node (ref "R29") (pin "2") (pinfunction "2_2") (pintype "passive"))
    )
    (net (code "36") (name "Net-(IC3A-I1)") (class "Default")
      (node (ref "IC3") (pin "2") (pinfunction "I1_2") (pintype "input"))
      (node (ref "IC4") (pin "4") (pinfunction "O_4") (pintype "output"))
    )
    (net (code "37") (name "Net-(IC3A-O)") (class "Default")
      (node (ref "IC3") (pin "4") (pinfunction "O_4") (pintype "output"))
      (node (ref "Q3") (pin "1") (pinfunction "G_1") (pintype "passive"))
    )
    (net (code "38") (name "Net-(IC6-CLK)") (class "Default")
      (node (ref "C20") (pin "1") (pinfunction "1_1") (pintype "passive"))
      (node (ref "IC6") (pin "1") (pinfunction "CLK_1") (pintype "input"))
      (node (ref "R11") (pin "1") (pinfunction "1_1") (pintype "passive"))
      (node (ref "R31") (pin "2") (pinfunction "2_2") (pintype "passive"))
    )
    (net (code "39") (name "Net-(IC6-D)") (class "Default")
      (node (ref "IC6") (pin "2") (pinfunction "D_2") (pintype "input"))
      (node (ref "IC6") (pin "3") (pinfunction "~{Q}_3") (pintype "output"))
    )
    (net (code "40") (name "Net-(IC7A-I1)") (class "Default")
      (node (ref "IC7") (pin "2") (pinfunction "I1_2") (pintype "input"))
      (node (ref "R15") (pin "2") (pinfunction "2_2") (pintype "passive"))
    )
    (net (code "41") (name "Net-(IC7A-O)") (class "Default")
      (node (ref "IC7") (pin "4") (pinfunction "O_4") (pintype "output"))
      (node (ref "Q6") (pin "1") (pinfunction "G_1") (pintype "passive"))
      (node (ref "Q8") (pin "1") (pinfunction "G_1") (pintype "passive"))
    )
    (net (code "42") (name "Net-(IC9A-I1)") (class "Default")
      (node (ref "IC9") (pin "2") (pinfunction "I1_2") (pintype "input"))
      (node (ref "R15") (pin "1") (pinfunction "1_1") (pintype "passive"))
      (node (ref "R18") (pin "1") (pinfunction "1_1") (pintype "passive"))
    )
    (net (code "43") (name "Net-(IC9A-O)") (class "Default")
      (node (ref "IC9") (pin "4") (pinfunction "O_4") (pintype "output"))
      (node (ref "Q5") (pin "1") (pinfunction "G_1") (pintype "passive"))
      (node (ref "Q7") (pin "1") (pinfunction "G_1") (pintype "passive"))
    )
    (net (code "44") (name "Net-(LEDGREEN53-PadA)") (class "Default")
      (node (ref "LEDGREEN53") (pin "A") (pinfunction "A_A") (pintype "passive"))
      (node (ref "R13") (pin "2") (pinfunction "2_2") (pintype "passive"))
    )
    (net (code "45") (name "Net-(LEDRED53-PadA)") (class "Default")
      (node (ref "LEDRED53") (pin "A") (pinfunction "A_A") (pintype "passive"))
      (node (ref "R14") (pin "2") (pinfunction "2_2") (pintype "passive"))
    )
    (net (code "46") (name "Net-(Q1A-D)") (class "Default")
      (node (ref "Q1") (pin "6") (pinfunction "D_6") (pintype "passive"))
      (node (ref "SW1") (pin "2") (pinfunction "P_2") (pintype "passive"))
    )
    (net (code "47") (name "Net-(Q1A-G)") (class "Default")
      (node (ref "C2") (pin "1") (pinfunction "1_1") (pintype "passive"))
      (node (ref "C3") (pin "1") (pinfunction "1_1") (pintype "passive"))
      (node (ref "L1") (pin "2") (pinfunction "2_2") (pintype "passive"))
      (node (ref "Q1") (pin "2") (pinfunction "G_2") (pintype "passive"))
      (node (ref "Q1") (pin "3") (pinfunction "D_3") (pintype "passive"))
      (node (ref "R2") (pin "2") (pinfunction "2_2") (pintype "passive"))
      (node (ref "U1") (pin "4") (pinfunction "VIN_4") (pintype "power_in"))
    )
    (net (code "48") (name "Net-(Q4-B)") (class "Default")
      (node (ref "C23") (pin "2") (pinfunction "2_2") (pintype "passive"))
      (node (ref "Q4") (pin "1") (pinfunction "B_1") (pintype "passive"))
      (node (ref "R20") (pin "1") (pinfunction "1_1") (pintype "passive"))
      (node (ref "R25") (pin "2") (pinfunction "2_2") (pintype "passive"))
    )
    (net (code "49") (name "Net-(Q4-E)") (class "Default")
      (node (ref "C25") (pin "1") (pinfunction "1_1") (pintype "passive"))
      (node (ref "Q4") (pin "2") (pinfunction "E_2") (pintype "passive"))
      (node (ref "R26") (pin "2") (pinfunction "2_2") (pintype "passive"))
    )
    (net (code "50") (name "Net-(Q5-D)") (class "Default")
      (node (ref "L2") (pin "1") (pinfunction "1_1") (pintype "passive"))
      (node (ref "Q5") (pin "3") (pinfunction "D_3") (pintype "passive"))
      (node (ref "Q7") (pin "3") (pinfunction "D_3") (pintype "passive"))
    )
    (net (code "51") (name "Net-(Q6-D)") (class "Default")
      (node (ref "L3") (pin "1") (pinfunction "1_1") (pintype "passive"))
      (node (ref "Q6") (pin "3") (pinfunction "D_3") (pintype "passive"))
      (node (ref "Q8") (pin "3") (pinfunction "D_3") (pintype "passive"))
    )
    (net (code "52") (name "Net-(R17-Pad2)") (class "Default")
      (node (ref "R17") (pin "2") (pinfunction "2_2") (pintype "passive"))
      (node (ref "X3") (pin "SIG") (pinfunction "SIG_SIG") (pintype "bidirectional"))
    )
    (net (code "53") (name "Net-(U1-PROG)") (class "Default")
      (node (ref "R4") (pin "2") (pinfunction "2_2") (pintype "passive"))
      (node (ref "U1") (pin "5") (pinfunction "PROG_5") (pintype "input"))
    )
    (net (code "54") (name "PDI-CLK") (class "Default")
      (node (ref "IC1") (pin "35") (pinfunction "RESET(PDI_CLK)_35") (pintype "bidirectional"))
      (node (ref "R1") (pin "1") (pinfunction "1_1") (pintype "passive"))
      (node (ref "X1") (pin "5") (pinfunction "5_5") (pintype "passive"))
    )
    (net (code "55") (name "PDI-DATA") (class "Default")
      (node (ref "IC1") (pin "34") (pinfunction "PDI_34") (pintype "bidirectional"))
      (node (ref "X1") (pin "1") (pinfunction "1_1") (pintype "passive"))
    )
    (net (code "56") (name "RBUTTON") (class "Default")
      (node (ref "IC1") (pin "2") (pinfunction "PA6_2") (pintype "bidirectional"))
      (node (ref "RBTN53") (pin "4") (pinfunction "4_4") (pintype "passive"))
    )
    (net (code "57") (name "RSSI") (class "Default")
      (node (ref "C32") (pin "1") (pinfunction "1_1") (pintype "passive"))
      (node (ref "IC1") (pin "41") (pinfunction "PA1_41") (pintype "bidirectional"))
      (node (ref "R10") (pin "2") (pinfunction "2_2") (pintype "passive"))
      (node (ref "R9") (pin "1") (pinfunction "1_1") (pintype "passive"))
    )
    (net (code "58") (name "SUBCARRIER-OOK{slash}MOD") (class "Default")
      (node (ref "IC1") (pin "15") (pinfunction "PC5_15") (pintype "bidirectional"))
      (node (ref "R18") (pin "2") (pinfunction "2_2") (pintype "passive"))
      (node (ref "R29") (pin "1") (pinfunction "1_1") (pintype "passive"))
      (node (ref "R30") (pin "2") (pinfunction "2_2") (pintype "passive"))
    )
    (net (code "59") (name "SUBCARRIER-PSK") (class "Default")
      (node (ref "IC1") (pin "14") (pinfunction "PC4_14") (pintype "bidirectional"))
      (node (ref "IC4") (pin "2") (pinfunction "I1_2") (pintype "input"))
    )
    (net (code "60") (name "USB-DM") (class "Default")
      (node (ref "IC1") (pin "26") (pinfunction "PD6_26") (pintype "bidirectional"))
      (node (ref "J1") (pin "D-") (pinfunction "D-_D-") (pintype "bidirectional"))
    )
    (net (code "61") (name "USB-DP") (class "Default")
      (node (ref "IC1") (pin "27") (pinfunction "PD7_27") (pintype "bidirectional"))
      (node (ref "J1") (pin "D+") (pinfunction "D+_D+") (pintype "bidirectional"))
    )
    (net (code "62") (name "USB-SENSE") (class "Default")
      (node (ref "IC1") (pin "25") (pinfunction "PD5_25") (pintype "bidirectional"))
      (node (ref "R2") (pin "1") (pinfunction "1_1") (pintype "passive"))
      (node (ref "R3") (pin "2") (pinfunction "2_2") (pintype "passive"))
    )
    (net (code "63") (name "VCC") (class "Default")
      (node (ref "C8") (pin "1") (pinfunction "1_1") (pintype "passive"))
      (node (ref "IC2") (pin "3") (pinfunction "IN_3") (pintype "input"))
      (node (ref "Q1") (pin "1") (pinfunction "S_1") (pintype "passive"))
      (node (ref "Q1") (pin "4") (pinfunction "S_4") (pintype "passive"))
      (node (ref "Q1") (pin "5") (pinfunction "G_5") (pintype "passive"))
      (node (ref "SW1") (pin "1") (pinfunction "O_1") (pintype "passive"))
    )
    (net (code "64") (name "unconnected-(IC1-PA0-Pad40)") (class "Default")
      (node (ref "IC1") (pin "40") (pinfunction "PA0_40") (pintype "bidirectional"))
    )
    (net (code "65") (name "unconnected-(IC1-PC3-Pad13)") (class "Default")
      (node (ref "IC1") (pin "13") (pinfunction "PC3_13") (pintype "bidirectional"))
    )
    (net (code "66") (name "unconnected-(IC1-PC7-Pad17)") (class "Default")
      (node (ref "IC1") (pin "17") (pinfunction "PC7_17") (pintype "bidirectional"))
    )
    (net (code "67") (name "unconnected-(IC1-PE1-Pad29)") (class "Default")
      (node (ref "IC1") (pin "29") (pinfunction "PE1_29") (pintype "bidirectional"))
    )
    (net (code "68") (name "unconnected-(LBUTTON53-Pad2)") (class "Default")
      (node (ref "LBUTTON53") (pin "2") (pinfunction "2_2") (pintype "passive"))
    )
    (net (code "69") (name "unconnected-(LBUTTON53-Pad3)") (class "Default")
      (node (ref "LBUTTON53") (pin "3") (pinfunction "3_3") (pintype "passive"))
    )
    (net (code "70") (name "unconnected-(RBTN53-Pad2)") (class "Default")
      (node (ref "RBTN53") (pin "2") (pinfunction "2_2") (pintype "passive"))
    )
    (net (code "71") (name "unconnected-(RBTN53-Pad3)") (class "Default")
      (node (ref "RBTN53") (pin "3") (pinfunction "3_3") (pintype "passive"))
    )
    (net (code "72") (name "unconnected-(X3-GND-PadGND2)") (class "Default")
      (node (ref "X3") (pin "GND2") (pinfunction "GND_GND2") (pintype "bidirectional"))
    )
    (net (code "73") (name "~{BRIDGE-CLK}") (class "Default")
      (node (ref "IC1") (pin "10") (pinfunction "PC0_10") (pintype "bidirectional"))
      (node (ref "IC7") (pin "1") (pinfunction "I0_1") (pintype "input"))
      (node (ref "R16") (pin "1") (pinfunction "1_1") (pintype "passive"))
    )
  )
)
